# ESP32-2-System.net
KiCad netlist of a schematic drawn in Altium Designer
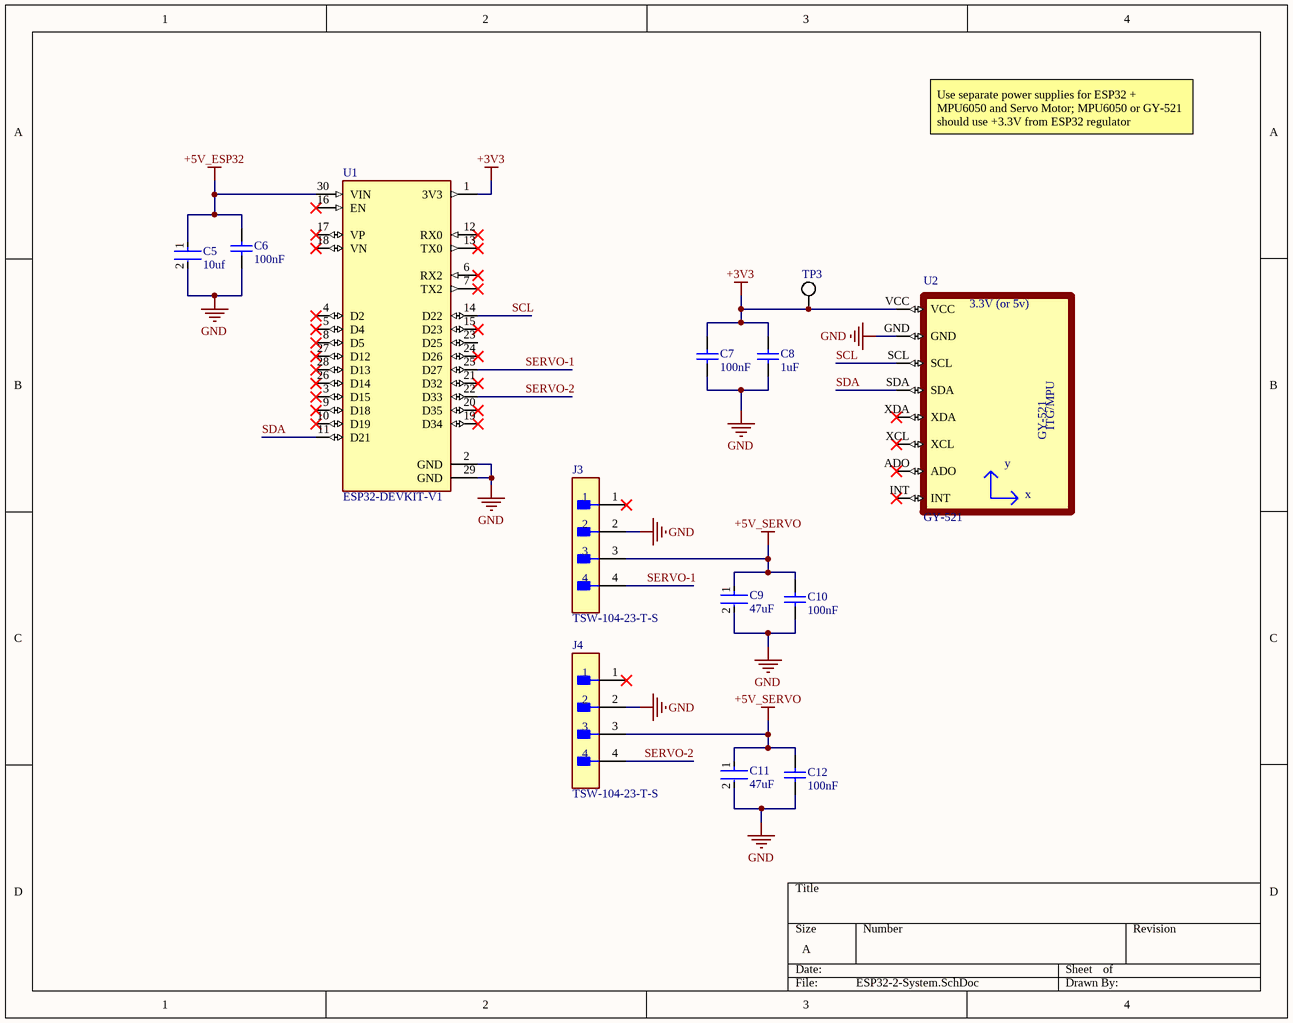
[diagram p0: ESP32-2-System.SchDoc]

(export (version "E")
  (design (tool "Eeschema 10.0.6"))
  (components
    (comp (ref "C5")
      (value "10uf")
      (footprint "FP-GCJ31C-0_3-IPC_C")
      (description "Cap Ceramic 10uF 10V X7R 10% Pad SMD 1206 Soft Termination  +125°C Automotive T/R")
      (fields (field (name "TOLERANCE") "10%") (field (name "VOLTAGE") "10V"))
      (libsource (lib "Altium Content Vault") (part "b4654b650e69147ec39a6b967a45e02"))
    )
    (comp (ref "C6")
      (value "100nF")
      (footprint "CAPC1206(3216)170_L")
      (description "CAP 100nF 50V ±10% 1206 (3216 Metric) Thickness 1.7mm SMD")
      (fields (field (name "TOLERANCE") "Â±10%"))
      (libsource (lib "Altium Content Vault") (part "CAP"))
    )
    (comp (ref "C7")
      (value "100nF")
      (footprint "CAPC1206(3216)170_L")
      (description "CAP 100nF 50V ±10% 1206 (3216 Metric) Thickness 1.7mm SMD")
      (fields (field (name "TOLERANCE") "Â±10%"))
      (libsource (lib "Altium Content Vault") (part "CAP"))
    )
    (comp (ref "C8")
      (value "1uF")
      (footprint "CAPC1206(3216)170_L")
      (description "CAP 1uF 16V ±10% 1206 (3216 Metric) Thickness 1.7mm SMD")
      (fields (field (name "TOLERANCE") "Â±10%"))
      (libsource (lib "Altium Content Vault") (part "CAP"))
    )
    (comp (ref "C9")
      (value "47uF")
      (footprint "FP-CL32-IPC_C")
      (description "Cap Ceramic 47uF 16V X5R ±20% SMD 1210 +85°C Embossed T/R; CL32A476MOJNNWE")
      (libsource (lib "Altium Content Vault") (part "b4654b650e69147ec39a6b967a45e02"))
    )
    (comp (ref "C10")
      (value "100nF")
      (footprint "CAPC1206(3216)170_L")
      (description "CAP 100nF 50V ±10% 1206 (3216 Metric) Thickness 1.7mm SMD")
      (fields (field (name "TOLERANCE") "Â±10%"))
      (libsource (lib "Altium Content Vault") (part "CAP"))
    )
    (comp (ref "C11")
      (value "47uF")
      (footprint "FP-CL32-IPC_C")
      (description "Cap Ceramic 47uF 16V X5R ±20% SMD 1210 +85°C Embossed T/R; CL32A476MOJNNWE")
      (libsource (lib "Altium Content Vault") (part "b4654b650e69147ec39a6b967a45e02"))
    )
    (comp (ref "C12")
      (value "100nF")
      (footprint "CAPC1206(3216)170_L")
      (description "CAP 100nF 50V ±10% 1206 (3216 Metric) Thickness 1.7mm SMD")
      (fields (field (name "TOLERANCE") "Â±10%"))
      (libsource (lib "Altium Content Vault") (part "CAP"))
    )
    (comp (ref "J3")
      (value "TSW-104-23-T-S")
      (footprint "FP-TSW-104-23-T-S-MFG")
      (description "CONN HEADER VERT 4POS 2.54MM")
      (libsource (lib "Altium Content Vault") (part "f33e0d423099bbb9e64512431cdbdf7"))
    )
    (comp (ref "J4")
      (value "TSW-104-23-T-S")
      (footprint "FP-TSW-104-23-T-S-MFG")
      (description "CONN HEADER VERT 4POS 2.54MM")
      (libsource (lib "Altium Content Vault") (part "f33e0d423099bbb9e64512431cdbdf7"))
    )
    (comp (ref "TP3")
      (value "Test Point")
      (footprint "Test Point")
      (libsource (lib "University of California, Riverside") (part "Test Point"))
    )
    (comp (ref "U1")
      (value "ESP32-DEVKIT-V1")
      (footprint "MODULE_ESP32_DEVKIT_V1")
      (fields (field (name "MF") "Do it"))
      (libsource (lib "University of California, Riverside") (part "ESP32-DEVKIT-V1"))
    )
    (comp (ref "U2")
      (value "GY-521")
      (footprint "GY-521")
      (description "Triple Axis Accelerometer Gyro Breakout")
      (fields (field (name "MF") "GODREAM FORDREAM CO., LIMITED"))
      (libsource (lib "University of California, Riverside") (part "GY-521"))
    )
  )
  (nets
    (net (code "1") (name "+3V3") (class "Default")
      (node (ref "C7") (pin "2") (pinfunction "2_2") (pintype "passive"))
      (node (ref "C8") (pin "2") (pinfunction "2_2") (pintype "passive"))
      (node (ref "TP3") (pin "1") (pinfunction "1_1") (pintype "passive"))
      (node (ref "U1") (pin "1") (pinfunction "3V3_1") (pintype "output"))
      (node (ref "U2") (pin "VCC") (pinfunction "VCC_VCC") (pintype "bidirectional"))
    )
    (net (code "2") (name "+5V_ESP32") (class "Default")
      (node (ref "C5") (pin "1") (pinfunction "1_1") (pintype "passive"))
      (node (ref "C6") (pin "2") (pinfunction "2_2") (pintype "passive"))
      (node (ref "U1") (pin "30") (pinfunction "VIN_30") (pintype "input"))
    )
    (net (code "3") (name "+5V_SERVO") (class "Default")
      (node (ref "C10") (pin "2") (pinfunction "2_2") (pintype "passive"))
      (node (ref "C11") (pin "1") (pinfunction "1_1") (pintype "passive"))
      (node (ref "C12") (pin "2") (pinfunction "2_2") (pintype "passive"))
      (node (ref "C9") (pin "1") (pinfunction "1_1") (pintype "passive"))
      (node (ref "J3") (pin "3") (pinfunction "3_3") (pintype "passive"))
      (node (ref "J4") (pin "3") (pinfunction "3_3") (pintype "passive"))
    )
    (net (code "4") (name "/SCL") (class "Default")
      (node (ref "U1") (pin "14") (pinfunction "D22_14") (pintype "bidirectional"))
      (node (ref "U2") (pin "SCL") (pinfunction "SCL_SCL") (pintype "bidirectional"))
    )
    (net (code "5") (name "/SDA") (class "Default")
      (node (ref "U1") (pin "11") (pinfunction "D21_11") (pintype "bidirectional"))
      (node (ref "U2") (pin "SDA") (pinfunction "SDA_SDA") (pintype "bidirectional"))
    )
    (net (code "6") (name "/SERVO-1") (class "Default")
      (node (ref "J3") (pin "4") (pinfunction "4_4") (pintype "passive"))
      (node (ref "U1") (pin "25") (pinfunction "D27_25") (pintype "bidirectional"))
    )
    (net (code "7") (name "/SERVO-2") (class "Default")
      (node (ref "J4") (pin "4") (pinfunction "4_4") (pintype "passive"))
      (node (ref "U1") (pin "22") (pinfunction "D33_22") (pintype "bidirectional"))
    )
    (net (code "8") (name "GND") (class "Default")
      (node (ref "C10") (pin "1") (pinfunction "1_1") (pintype "passive"))
      (node (ref "C11") (pin "2") (pinfunction "2_2") (pintype "passive"))
      (node (ref "C12") (pin "1") (pinfunction "1_1") (pintype "passive"))
      (node (ref "C5") (pin "2") (pinfunction "2_2") (pintype "passive"))
      (node (ref "C6") (pin "1") (pinfunction "1_1") (pintype "passive"))
      (node (ref "C7") (pin "1") (pinfunction "1_1") (pintype "passive"))
      (node (ref "C8") (pin "1") (pinfunction "1_1") (pintype "passive"))
      (node (ref "C9") (pin "2") (pinfunction "2_2") (pintype "passive"))
      (node (ref "J3") (pin "2") (pinfunction "2_2") (pintype "passive"))
      (node (ref "J4") (pin "2") (pinfunction "2_2") (pintype "passive"))
      (node (ref "U1") (pin "2") (pinfunction "GND_2") (pintype "power_in"))
      (node (ref "U1") (pin "29") (pinfunction "GND_29") (pintype "power_in"))
      (node (ref "U2") (pin "GND") (pinfunction "GND_GND") (pintype "bidirectional"))
    )
    (net (code "9") (name "unconnected-(J3-Pad1)") (class "Default")
      (node (ref "J3") (pin "1") (pinfunction "1_1") (pintype "passive+no_connect"))
    )
    (net (code "10") (name "unconnected-(J4-Pad1)") (class "Default")
      (node (ref "J4") (pin "1") (pinfunction "1_1") (pintype "passive+no_connect"))
    )
    (net (code "11") (name "unconnected-(U1-D2-Pad4)") (class "Default")
      (node (ref "U1") (pin "4") (pinfunction "D2_4") (pintype "bidirectional+no_connect"))
    )
    (net (code "12") (name "unconnected-(U1-D4-Pad5)") (class "Default")
      (node (ref "U1") (pin "5") (pinfunction "D4_5") (pintype "bidirectional+no_connect"))
    )
    (net (code "13") (name "unconnected-(U1-D5-Pad8)") (class "Default")
      (node (ref "U1") (pin "8") (pinfunction "D5_8") (pintype "bidirectional+no_connect"))
    )
    (net (code "14") (name "unconnected-(U1-D12-Pad27)") (class "Default")
      (node (ref "U1") (pin "27") (pinfunction "D12_27") (pintype "bidirectional+no_connect"))
    )
    (net (code "15") (name "unconnected-(U1-D13-Pad28)") (class "Default")
      (node (ref "U1") (pin "28") (pinfunction "D13_28") (pintype "bidirectional+no_connect"))
    )
    (net (code "16") (name "unconnected-(U1-D14-Pad26)") (class "Default")
      (node (ref "U1") (pin "26") (pinfunction "D14_26") (pintype "bidirectional+no_connect"))
    )
    (net (code "17") (name "unconnected-(U1-D15-Pad3)") (class "Default")
      (node (ref "U1") (pin "3") (pinfunction "D15_3") (pintype "bidirectional+no_connect"))
    )
    (net (code "18") (name "unconnected-(U1-D18-Pad9)") (class "Default")
      (node (ref "U1") (pin "9") (pinfunction "D18_9") (pintype "bidirectional+no_connect"))
    )
    (net (code "19") (name "unconnected-(U1-D19-Pad10)") (class "Default")
      (node (ref "U1") (pin "10") (pinfunction "D19_10") (pintype "bidirectional+no_connect"))
    )
    (net (code "20") (name "unconnected-(U1-D23-Pad15)") (class "Default")
      (node (ref "U1") (pin "15") (pinfunction "D23_15") (pintype "bidirectional+no_connect"))
    )
    (net (code "21") (name "unconnected-(U1-D25-Pad23)") (class "Default")
      (node (ref "U1") (pin "23") (pinfunction "D25_23") (pintype "bidirectional"))
    )
    (net (code "22") (name "unconnected-(U1-D26-Pad24)") (class "Default")
      (node (ref "U1") (pin "24") (pinfunction "D26_24") (pintype "bidirectional+no_connect"))
    )
    (net (code "23") (name "unconnected-(U1-D32-Pad21)") (class "Default")
      (node (ref "U1") (pin "21") (pinfunction "D32_21") (pintype "bidirectional+no_connect"))
    )
    (net (code "24") (name "unconnected-(U1-D34-Pad19)") (class "Default")
      (node (ref "U1") (pin "19") (pinfunction "D34_19") (pintype "bidirectional+no_connect"))
    )
    (net (code "25") (name "unconnected-(U1-D35-Pad20)") (class "Default")
      (node (ref "U1") (pin "20") (pinfunction "D35_20") (pintype "bidirectional+no_connect"))
    )
    (net (code "26") (name "unconnected-(U1-EN-Pad16)") (class "Default")
      (node (ref "U1") (pin "16") (pinfunction "EN_16") (pintype "input+no_connect"))
    )
    (net (code "27") (name "unconnected-(U1-RX0-Pad12)") (class "Default")
      (node (ref "U1") (pin "12") (pinfunction "RX0_12") (pintype "input+no_connect"))
    )
    (net (code "28") (name "unconnected-(U1-RX2-Pad6)") (class "Default")
      (node (ref "U1") (pin "6") (pinfunction "RX2_6") (pintype "input+no_connect"))
    )
    (net (code "29") (name "unconnected-(U1-TX0-Pad13)") (class "Default")
      (node (ref "U1") (pin "13") (pinfunction "TX0_13") (pintype "output+no_connect"))
    )
    (net (code "30") (name "unconnected-(U1-TX2-Pad7)") (class "Default")
      (node (ref "U1") (pin "7") (pinfunction "TX2_7") (pintype "output+no_connect"))
    )
    (net (code "31") (name "unconnected-(U1-VN-Pad18)") (class "Default")
      (node (ref "U1") (pin "18") (pinfunction "VN_18") (pintype "bidirectional+no_connect"))
    )
    (net (code "32") (name "unconnected-(U1-VP-Pad17)") (class "Default")
      (node (ref "U1") (pin "17") (pinfunction "VP_17") (pintype "bidirectional+no_connect"))
    )
    (net (code "33") (name "unconnected-(U2-PadADO)") (class "Default")
      (node (ref "U2") (pin "ADO") (pinfunction "ADO_ADO") (pintype "bidirectional+no_connect"))
    )
    (net (code "34") (name "unconnected-(U2-PadINT)") (class "Default")
      (node (ref "U2") (pin "INT") (pinfunction "INT_INT") (pintype "bidirectional+no_connect"))
    )
    (net (code "35") (name "unconnected-(U2-PadXCL)") (class "Default")
      (node (ref "U2") (pin "XCL") (pinfunction "XCL_XCL") (pintype "bidirectional+no_connect"))
    )
    (net (code "36") (name "unconnected-(U2-PadXDA)") (class "Default")
      (node (ref "U2") (pin "XDA") (pinfunction "XDA_XDA") (pintype "bidirectional+no_connect"))
    )
  )
)
